# keymatrix.net
KiCad netlist of a schematic drawn in EAGLE
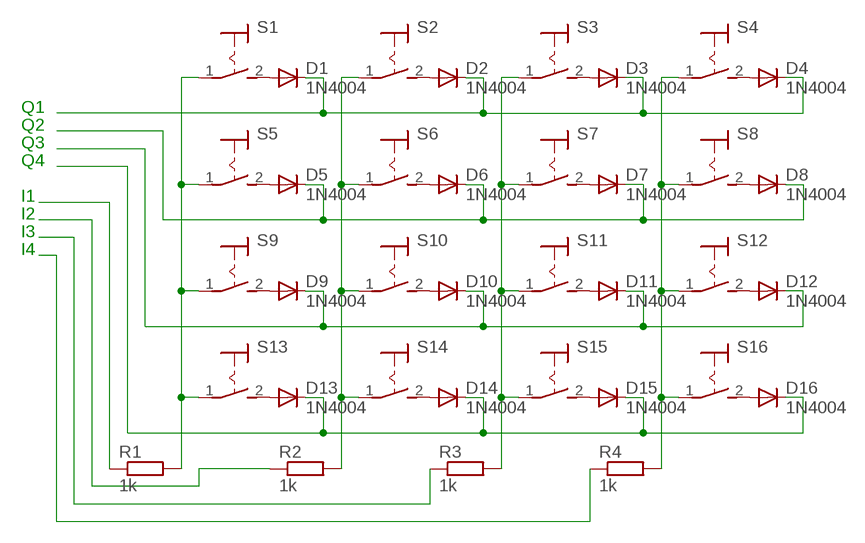
[diagram p0: schematic, sheet 1]

(export (version "E")
  (design (tool "Eeschema 10.0.6"))
  (components
    (comp (ref "D1")
      (value "1N4004")
      (footprint "eagle-import:DO41-10")
      (libsource (lib "eagle-import") (part "1N4004"))
    )
    (comp (ref "D2")
      (value "1N4004")
      (footprint "eagle-import:DO41-10")
      (libsource (lib "eagle-import") (part "1N4004"))
    )
    (comp (ref "D3")
      (value "1N4004")
      (footprint "eagle-import:DO41-10")
      (libsource (lib "eagle-import") (part "1N4004"))
    )
    (comp (ref "D4")
      (value "1N4004")
      (footprint "eagle-import:DO41-10")
      (libsource (lib "eagle-import") (part "1N4004"))
    )
    (comp (ref "D5")
      (value "1N4004")
      (footprint "eagle-import:DO41-10")
      (libsource (lib "eagle-import") (part "1N4004"))
    )
    (comp (ref "D6")
      (value "1N4004")
      (footprint "eagle-import:DO41-10")
      (libsource (lib "eagle-import") (part "1N4004"))
    )
    (comp (ref "D7")
      (value "1N4004")
      (footprint "eagle-import:DO41-10")
      (libsource (lib "eagle-import") (part "1N4004"))
    )
    (comp (ref "D8")
      (value "1N4004")
      (footprint "eagle-import:DO41-10")
      (libsource (lib "eagle-import") (part "1N4004"))
    )
    (comp (ref "D9")
      (value "1N4004")
      (footprint "eagle-import:DO41-10")
      (libsource (lib "eagle-import") (part "1N4004"))
    )
    (comp (ref "D10")
      (value "1N4004")
      (footprint "eagle-import:DO41-10")
      (libsource (lib "eagle-import") (part "1N4004"))
    )
    (comp (ref "D11")
      (value "1N4004")
      (footprint "eagle-import:DO41-10")
      (libsource (lib "eagle-import") (part "1N4004"))
    )
    (comp (ref "D12")
      (value "1N4004")
      (footprint "eagle-import:DO41-10")
      (libsource (lib "eagle-import") (part "1N4004"))
    )
    (comp (ref "D13")
      (value "1N4004")
      (footprint "eagle-import:DO41-10")
      (libsource (lib "eagle-import") (part "1N4004"))
    )
    (comp (ref "D14")
      (value "1N4004")
      (footprint "eagle-import:DO41-10")
      (libsource (lib "eagle-import") (part "1N4004"))
    )
    (comp (ref "D15")
      (value "1N4004")
      (footprint "eagle-import:DO41-10")
      (libsource (lib "eagle-import") (part "1N4004"))
    )
    (comp (ref "D16")
      (value "1N4004")
      (footprint "eagle-import:DO41-10")
      (libsource (lib "eagle-import") (part "1N4004"))
    )
    (comp (ref "R1")
      (value "1k")
      (footprint "eagle-import:0204_7")
      (libsource (lib "eagle-import") (part "R-EU_0204/7"))
    )
    (comp (ref "R2")
      (value "1k")
      (footprint "eagle-import:0204_7")
      (libsource (lib "eagle-import") (part "R-EU_0204/7"))
    )
    (comp (ref "R3")
      (value "1k")
      (footprint "eagle-import:0204_7")
      (libsource (lib "eagle-import") (part "R-EU_0204/7"))
    )
    (comp (ref "R4")
      (value "1k")
      (footprint "eagle-import:0204_7")
      (libsource (lib "eagle-import") (part "R-EU_0204/7"))
    )
    (comp (ref "S1")
      (value "MS243")
      (footprint "eagle-import:MS243")
      (libsource (lib "eagle-import") (part "MS243"))
    )
    (comp (ref "S2")
      (value "MS243")
      (footprint "eagle-import:MS243")
      (libsource (lib "eagle-import") (part "MS243"))
    )
    (comp (ref "S3")
      (value "MS243")
      (footprint "eagle-import:MS243")
      (libsource (lib "eagle-import") (part "MS243"))
    )
    (comp (ref "S4")
      (value "MS243")
      (footprint "eagle-import:MS243")
      (libsource (lib "eagle-import") (part "MS243"))
    )
    (comp (ref "S5")
      (value "MS243")
      (footprint "eagle-import:MS243")
      (libsource (lib "eagle-import") (part "MS243"))
    )
    (comp (ref "S6")
      (value "MS243")
      (footprint "eagle-import:MS243")
      (libsource (lib "eagle-import") (part "MS243"))
    )
    (comp (ref "S7")
      (value "MS243")
      (footprint "eagle-import:MS243")
      (libsource (lib "eagle-import") (part "MS243"))
    )
    (comp (ref "S8")
      (value "MS243")
      (footprint "eagle-import:MS243")
      (libsource (lib "eagle-import") (part "MS243"))
    )
    (comp (ref "S9")
      (value "MS243")
      (footprint "eagle-import:MS243")
      (libsource (lib "eagle-import") (part "MS243"))
    )
    (comp (ref "S10")
      (value "MS243")
      (footprint "eagle-import:MS243")
      (libsource (lib "eagle-import") (part "MS243"))
    )
    (comp (ref "S11")
      (value "MS243")
      (footprint "eagle-import:MS243")
      (libsource (lib "eagle-import") (part "MS243"))
    )
    (comp (ref "S12")
      (value "MS243")
      (footprint "eagle-import:MS243")
      (libsource (lib "eagle-import") (part "MS243"))
    )
    (comp (ref "S13")
      (value "MS243")
      (footprint "eagle-import:MS243")
      (libsource (lib "eagle-import") (part "MS243"))
    )
    (comp (ref "S14")
      (value "MS243")
      (footprint "eagle-import:MS243")
      (libsource (lib "eagle-import") (part "MS243"))
    )
    (comp (ref "S15")
      (value "MS243")
      (footprint "eagle-import:MS243")
      (libsource (lib "eagle-import") (part "MS243"))
    )
    (comp (ref "S16")
      (value "MS243")
      (footprint "eagle-import:MS243")
      (libsource (lib "eagle-import") (part "MS243"))
    )
  )
  (nets
    (net (code "1") (name "Net-(D1-PadC)") (class "Default")
      (node (ref "D1") (pin "C") (pinfunction "C_C") (pintype "passive"))
      (node (ref "D2") (pin "C") (pinfunction "C_C") (pintype "passive"))
      (node (ref "D3") (pin "C") (pinfunction "C_C") (pintype "passive"))
      (node (ref "D4") (pin "C") (pinfunction "C_C") (pintype "passive"))
    )
    (net (code "2") (name "Net-(D5-PadC)") (class "Default")
      (node (ref "D5") (pin "C") (pinfunction "C_C") (pintype "passive"))
      (node (ref "D6") (pin "C") (pinfunction "C_C") (pintype "passive"))
      (node (ref "D7") (pin "C") (pinfunction "C_C") (pintype "passive"))
      (node (ref "D8") (pin "C") (pinfunction "C_C") (pintype "passive"))
    )
    (net (code "3") (name "Net-(D10-PadC)") (class "Default")
      (node (ref "D10") (pin "C") (pinfunction "C_C") (pintype "passive"))
      (node (ref "D11") (pin "C") (pinfunction "C_C") (pintype "passive"))
      (node (ref "D12") (pin "C") (pinfunction "C_C") (pintype "passive"))
      (node (ref "D9") (pin "C") (pinfunction "C_C") (pintype "passive"))
    )
    (net (code "4") (name "Net-(D13-PadC)") (class "Default")
      (node (ref "D13") (pin "C") (pinfunction "C_C") (pintype "passive"))
      (node (ref "D14") (pin "C") (pinfunction "C_C") (pintype "passive"))
      (node (ref "D15") (pin "C") (pinfunction "C_C") (pintype "passive"))
      (node (ref "D16") (pin "C") (pinfunction "C_C") (pintype "passive"))
    )
    (net (code "5") (name "Net-(S1-P)") (class "Default")
      (node (ref "R1") (pin "2") (pinfunction "2_2") (pintype "passive"))
      (node (ref "S1") (pin "1") (pinfunction "P_1") (pintype "passive"))
      (node (ref "S13") (pin "1") (pinfunction "P_1") (pintype "passive"))
      (node (ref "S5") (pin "1") (pinfunction "P_1") (pintype "passive"))
      (node (ref "S9") (pin "1") (pinfunction "P_1") (pintype "passive"))
    )
    (net (code "6") (name "Net-(S1-S)") (class "Default")
      (node (ref "D1") (pin "A") (pinfunction "A_A") (pintype "passive"))
      (node (ref "S1") (pin "2") (pinfunction "S_2") (pintype "passive"))
    )
    (net (code "7") (name "Net-(S2-S)") (class "Default")
      (node (ref "D2") (pin "A") (pinfunction "A_A") (pintype "passive"))
      (node (ref "S2") (pin "2") (pinfunction "S_2") (pintype "passive"))
    )
    (net (code "8") (name "Net-(S3-S)") (class "Default")
      (node (ref "D3") (pin "A") (pinfunction "A_A") (pintype "passive"))
      (node (ref "S3") (pin "2") (pinfunction "S_2") (pintype "passive"))
    )
    (net (code "9") (name "Net-(S4-S)") (class "Default")
      (node (ref "D4") (pin "A") (pinfunction "A_A") (pintype "passive"))
      (node (ref "S4") (pin "2") (pinfunction "S_2") (pintype "passive"))
    )
    (net (code "10") (name "Net-(S5-S)") (class "Default")
      (node (ref "D5") (pin "A") (pinfunction "A_A") (pintype "passive"))
      (node (ref "S5") (pin "2") (pinfunction "S_2") (pintype "passive"))
    )
    (net (code "11") (name "Net-(S6-S)") (class "Default")
      (node (ref "D6") (pin "A") (pinfunction "A_A") (pintype "passive"))
      (node (ref "S6") (pin "2") (pinfunction "S_2") (pintype "passive"))
    )
    (net (code "12") (name "Net-(S7-S)") (class "Default")
      (node (ref "D7") (pin "A") (pinfunction "A_A") (pintype "passive"))
      (node (ref "S7") (pin "2") (pinfunction "S_2") (pintype "passive"))
    )
    (net (code "13") (name "Net-(S8-S)") (class "Default")
      (node (ref "D8") (pin "A") (pinfunction "A_A") (pintype "passive"))
      (node (ref "S8") (pin "2") (pinfunction "S_2") (pintype "passive"))
    )
    (net (code "14") (name "Net-(S9-S)") (class "Default")
      (node (ref "D9") (pin "A") (pinfunction "A_A") (pintype "passive"))
      (node (ref "S9") (pin "2") (pinfunction "S_2") (pintype "passive"))
    )
    (net (code "15") (name "Net-(S10-P)") (class "Default")
      (node (ref "R2") (pin "2") (pinfunction "2_2") (pintype "passive"))
      (node (ref "S10") (pin "1") (pinfunction "P_1") (pintype "passive"))
      (node (ref "S14") (pin "1") (pinfunction "P_1") (pintype "passive"))
      (node (ref "S2") (pin "1") (pinfunction "P_1") (pintype "passive"))
      (node (ref "S6") (pin "1") (pinfunction "P_1") (pintype "passive"))
    )
    (net (code "16") (name "Net-(S10-S)") (class "Default")
      (node (ref "D10") (pin "A") (pinfunction "A_A") (pintype "passive"))
      (node (ref "S10") (pin "2") (pinfunction "S_2") (pintype "passive"))
    )
    (net (code "17") (name "Net-(S11-P)") (class "Default")
      (node (ref "R3") (pin "2") (pinfunction "2_2") (pintype "passive"))
      (node (ref "S11") (pin "1") (pinfunction "P_1") (pintype "passive"))
      (node (ref "S15") (pin "1") (pinfunction "P_1") (pintype "passive"))
      (node (ref "S3") (pin "1") (pinfunction "P_1") (pintype "passive"))
      (node (ref "S7") (pin "1") (pinfunction "P_1") (pintype "passive"))
    )
    (net (code "18") (name "Net-(S11-S)") (class "Default")
      (node (ref "D11") (pin "A") (pinfunction "A_A") (pintype "passive"))
      (node (ref "S11") (pin "2") (pinfunction "S_2") (pintype "passive"))
    )
    (net (code "19") (name "Net-(S12-P)") (class "Default")
      (node (ref "R4") (pin "2") (pinfunction "2_2") (pintype "passive"))
      (node (ref "S12") (pin "1") (pinfunction "P_1") (pintype "passive"))
      (node (ref "S16") (pin "1") (pinfunction "P_1") (pintype "passive"))
      (node (ref "S4") (pin "1") (pinfunction "P_1") (pintype "passive"))
      (node (ref "S8") (pin "1") (pinfunction "P_1") (pintype "passive"))
    )
    (net (code "20") (name "Net-(S12-S)") (class "Default")
      (node (ref "D12") (pin "A") (pinfunction "A_A") (pintype "passive"))
      (node (ref "S12") (pin "2") (pinfunction "S_2") (pintype "passive"))
    )
    (net (code "21") (name "Net-(S13-S)") (class "Default")
      (node (ref "D13") (pin "A") (pinfunction "A_A") (pintype "passive"))
      (node (ref "S13") (pin "2") (pinfunction "S_2") (pintype "passive"))
    )
    (net (code "22") (name "Net-(S14-S)") (class "Default")
      (node (ref "D14") (pin "A") (pinfunction "A_A") (pintype "passive"))
      (node (ref "S14") (pin "2") (pinfunction "S_2") (pintype "passive"))
    )
    (net (code "23") (name "Net-(S15-S)") (class "Default")
      (node (ref "D15") (pin "A") (pinfunction "A_A") (pintype "passive"))
      (node (ref "S15") (pin "2") (pinfunction "S_2") (pintype "passive"))
    )
    (net (code "24") (name "Net-(S16-S)") (class "Default")
      (node (ref "D16") (pin "A") (pinfunction "A_A") (pintype "passive"))
      (node (ref "S16") (pin "2") (pinfunction "S_2") (pintype "passive"))
    )
    (net (code "25") (name "unconnected-(R1-Pad1)") (class "Default")
      (node (ref "R1") (pin "1") (pinfunction "1_1") (pintype "passive"))
    )
    (net (code "26") (name "unconnected-(R2-Pad1)") (class "Default")
      (node (ref "R2") (pin "1") (pinfunction "1_1") (pintype "passive"))
    )
    (net (code "27") (name "unconnected-(R3-Pad1)") (class "Default")
      (node (ref "R3") (pin "1") (pinfunction "1_1") (pintype "passive"))
    )
    (net (code "28") (name "unconnected-(R4-Pad1)") (class "Default")
      (node (ref "R4") (pin "1") (pinfunction "1_1") (pintype "passive"))
    )
  )
)
